# ProProject_ad9959__2024-07-03.net
KiCad netlist of a schematic drawn in EasyEDA Pro
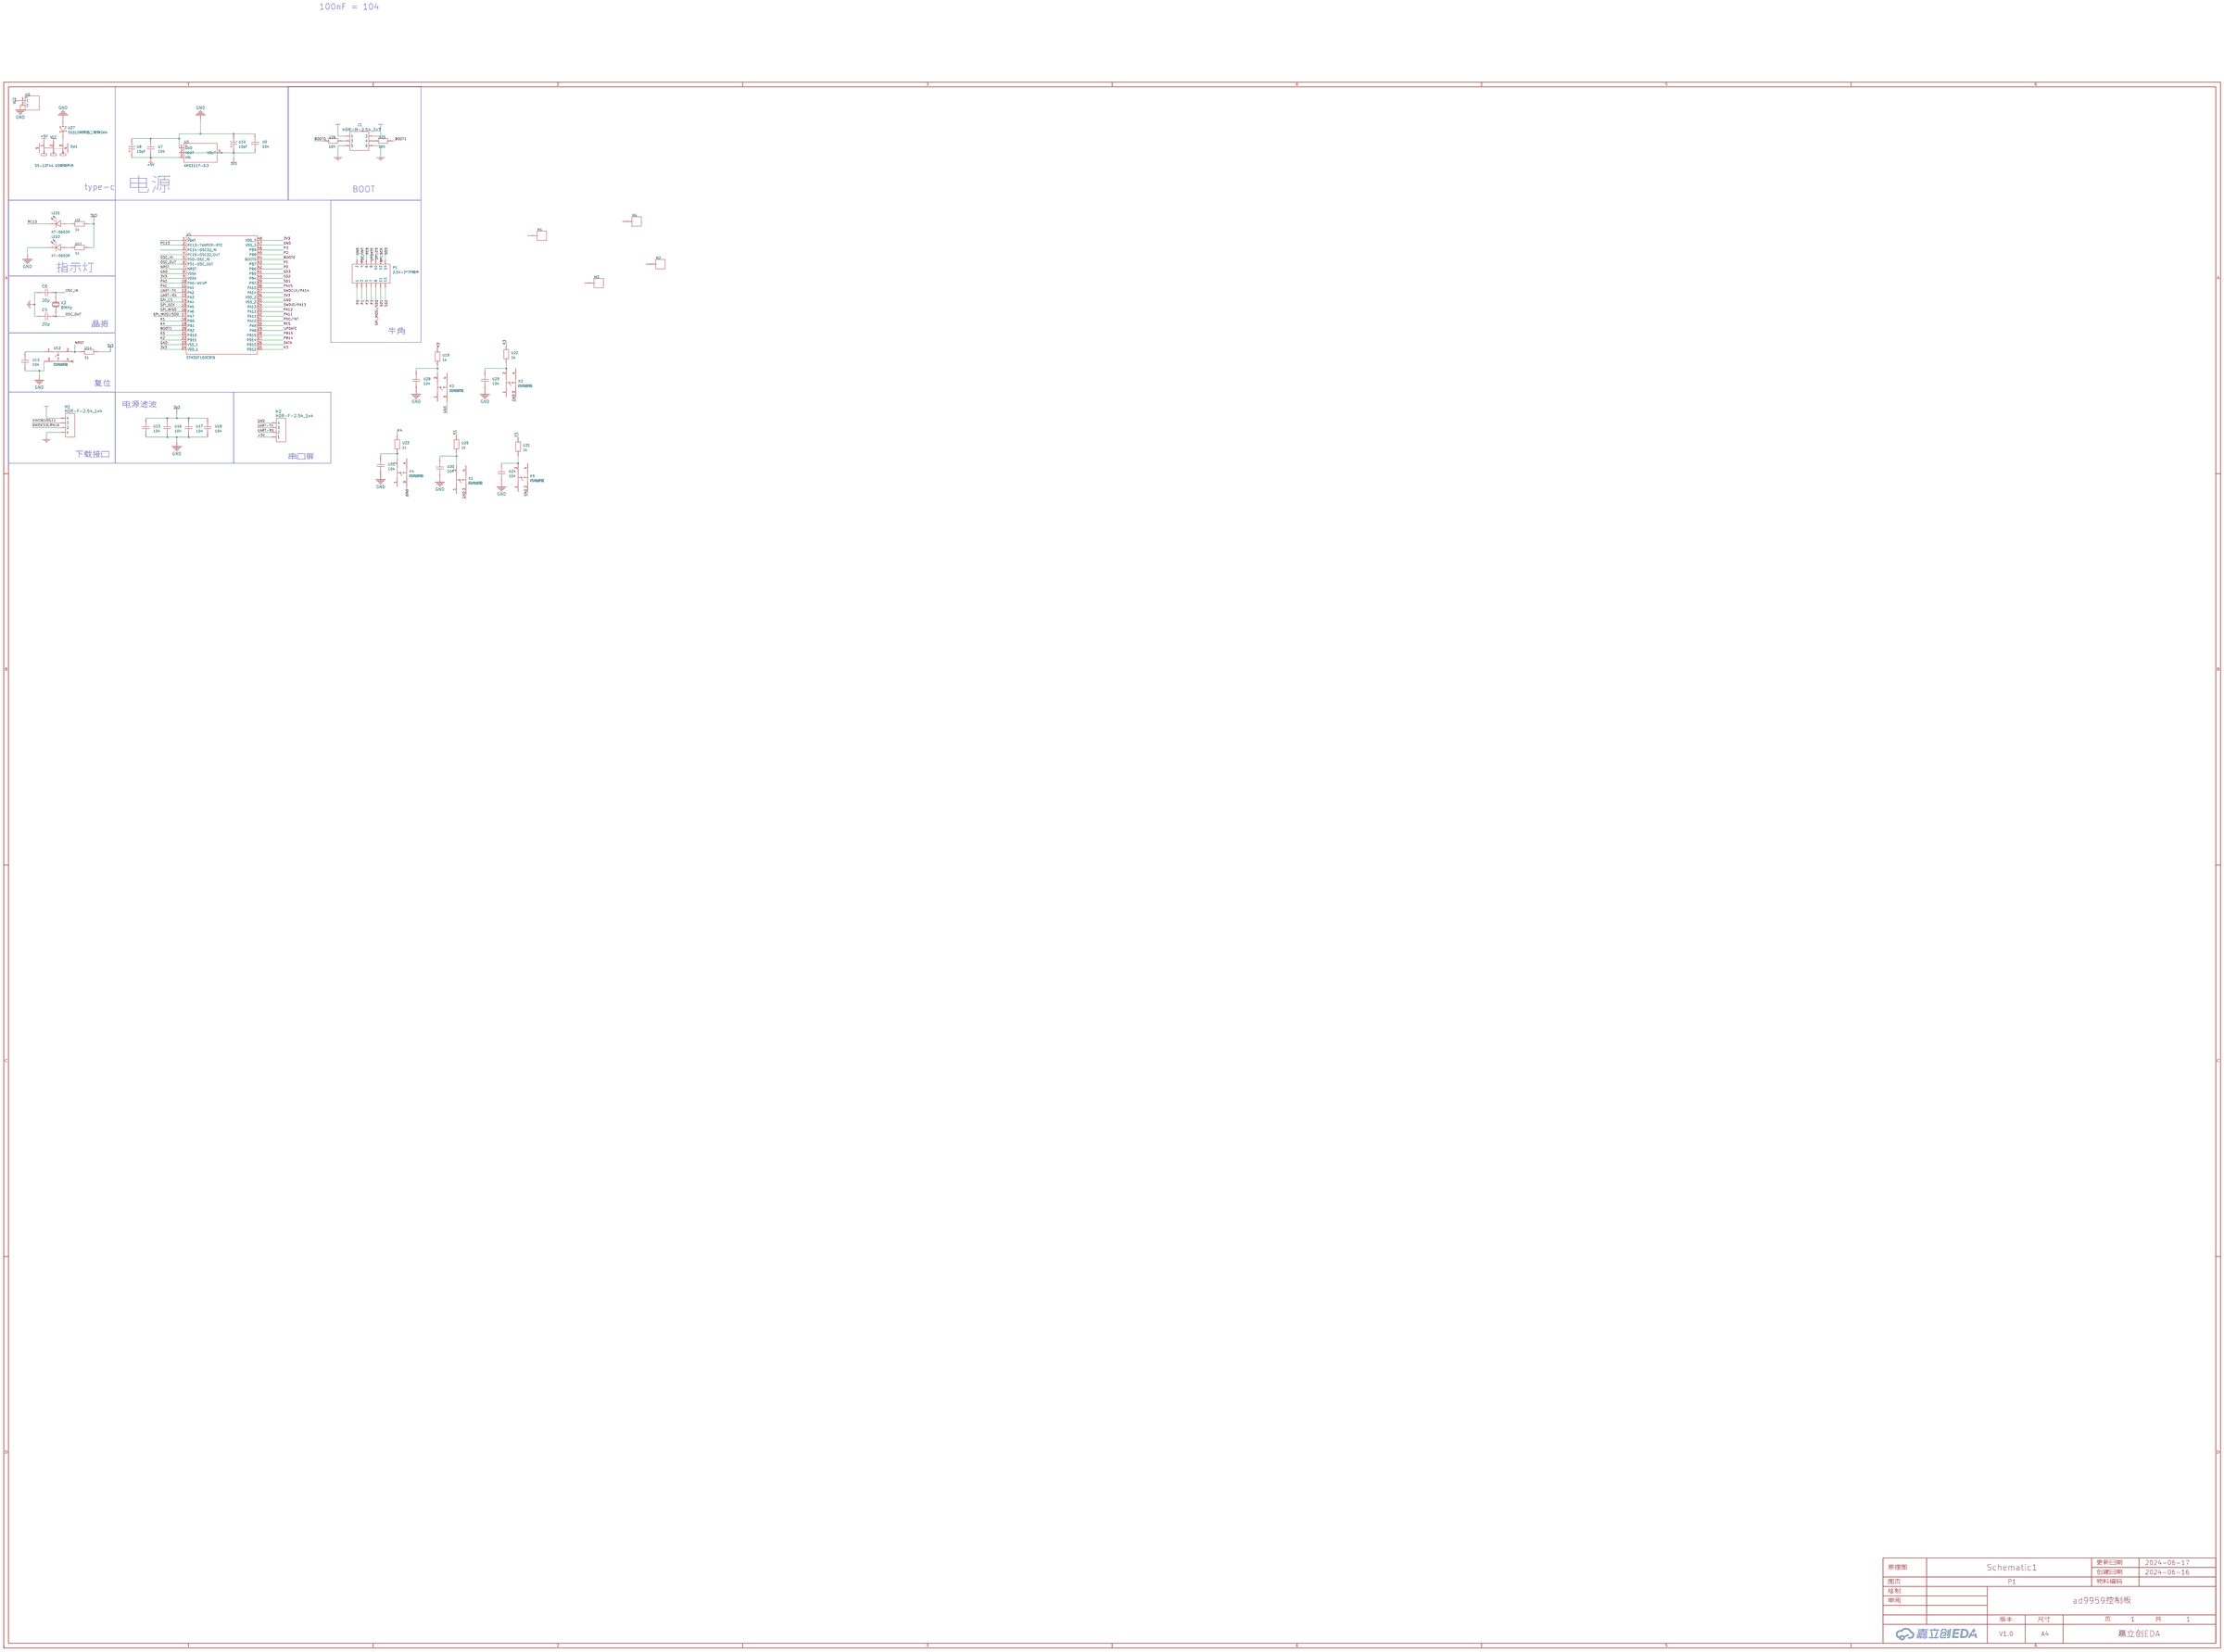
[diagram p0: schematic sheet]

(export (version "E")
  (design (tool "Eeschema 10.0.6"))
  (components
    (comp (ref "C5") (value "20p") (footprint "easyedapro:R0603") (libsource (lib "easyedapro") (part "20p")))
    (comp (ref "C6") (value "20p") (footprint "easyedapro:R0603") (libsource (lib "easyedapro") (part "20p")))
    (comp (ref "H1")
      (value "HDR-F-2.54_1x4")
      (footprint "easyedapro:HDR-F-2.54_1X4")
      (libsource (lib "easyedapro") (part "HDR-F-2.54_1x4"))
    )
    (comp (ref "H2")
      (value "HDR-F-2.54_1x4")
      (footprint "easyedapro:HDR-F-2.54_1X4")
      (libsource (lib "easyedapro") (part "HDR-F-2.54_1x4"))
    )
    (comp (ref "H3")
      (value "~")
      (footprint "easyedapro:HDR-TH_2P-P2.54-V-M-1")
      (libsource (lib "easyedapro") (part "210S-1*2P L=11.6MMGold-plated black"))
    )
    (comp (ref "J1")
      (value "HDR-M-2.54_2x3")
      (footprint "easyedapro:HDR-M-2.54_2X3")
      (libsource (lib "easyedapro") (part "HDR-M-2.54_2x3"))
    )
    (comp (ref "K1")
      (value "四角按键")
      (footprint "easyedapro:SW-SMD_4P-L6.0-W6.0-P4.50-LS9.2")
      (libsource (lib "easyedapro") (part "四角按键"))
    )
    (comp (ref "K2")
      (value "四角按键")
      (footprint "easyedapro:SW-SMD_4P-L6.0-W6.0-P4.50-LS9.2")
      (libsource (lib "easyedapro") (part "四角按键"))
    )
    (comp (ref "K3")
      (value "四角按键")
      (footprint "easyedapro:SW-SMD_4P-L6.0-W6.0-P4.50-LS9.2")
      (libsource (lib "easyedapro") (part "四角按键"))
    )
    (comp (ref "K4")
      (value "四角按键")
      (footprint "easyedapro:SW-SMD_4P-L6.0-W6.0-P4.50-LS9.2")
      (libsource (lib "easyedapro") (part "四角按键"))
    )
    (comp (ref "K5")
      (value "四角按键")
      (footprint "easyedapro:SW-SMD_4P-L6.0-W6.0-P4.50-LS9.2")
      (libsource (lib "easyedapro") (part "四角按键"))
    )
    (comp (ref "LED1")
      (value "KT-0603R")
      (footprint "easyedapro:LED0603-RD")
      (description "发光颜色:红色;功率:-;正向电流:-;主波长:-;二极管配置:-;透镜颜色:-;色温:-;发光角度:-;载带方式:-;工作温度:-40°C~+85°C;")
      (fields (field (name "Manufacturer") "KENTO"))
      (libsource (lib "easyedapro") (part "KT-0603R"))
    )
    (comp (ref "LED2")
      (value "KT-0603R")
      (footprint "easyedapro:LED0603-RD")
      (description "发光颜色:红色;功率:-;正向电流:-;主波长:-;二极管配置:-;透镜颜色:-;色温:-;发光角度:-;载带方式:-;工作温度:-40°C~+85°C;")
      (fields (field (name "Manufacturer") "KENTO"))
      (libsource (lib "easyedapro") (part "KT-0603R"))
    )
    (comp (ref "M1") (value "~") (footprint "easyedapro:M3定位孔") (libsource (lib "easyedapro") (part "定位孔")))
    (comp (ref "M2") (value "~") (footprint "easyedapro:M3定位孔") (libsource (lib "easyedapro") (part "定位孔")))
    (comp (ref "M3") (value "~") (footprint "easyedapro:M3定位孔") (libsource (lib "easyedapro") (part "定位孔")))
    (comp (ref "M4") (value "~") (footprint "easyedapro:M3定位孔") (libsource (lib "easyedapro") (part "定位孔")))
    (comp (ref "P1")
      (value "2.54-2*7P简牛")
      (footprint "easyedapro:IDC-TH_14P-P2.54-V-R2-C7-S2.54")
      (description "连接器类型:简牛座;间距:2.54mm;结构:2x7P;封装形式:直插;行距:2.54mm;排数:2;每排PIN数:7;触头材质:黄铜;触头镀层:金;")
      (fields (field (name "Manufacturer") "BOOMELE(博穆精密)"))
      (libsource (lib "easyedapro") (part "2.54-2*7P简牛"))
    )
    (comp (ref "SW1")
      (value "SS-12F44 G5拨动开关")
      (footprint "easyedapro:SW-TH_SS-12F44-G5")
      (description "拨动开关，柄高5mm")
      (libsource (lib "easyedapro") (part "SS-12F44-G5_C22465"))
    )
    (comp (ref "U1")
      (value "STM32F103C8T6")
      (footprint "easyedapro:LQFP-48_L7.0-W7.0-P0.50-LS9.0-BL")
      (description "CPU内核:ARM-M3;程序存储容量:64KB;RAM总容量:20KB;GPIO端口数量:37;工作电压范围:2V~3.6V;CPU最大主频:72MHz;程序存储器类型:FLASH;")
      (fields (field (name "Manufacturer") "ST(意法半导体)"))
      (libsource (lib "easyedapro") (part "STM32F103C8T6"))
    )
    (comp (ref "U3")
      (value "1k")
      (footprint "easyedapro:R0603")
      (description "电阻类型:薄膜电阻;阻值:7.41kΩ;精度:±0.5%;功率:100mW;温度系数:±50ppm/°C;")
      (fields (field (name "Manufacturer Part") "RT0603DRE077K41L") (field (name "Manufacturer") "YAGEO(国巨)"))
      (libsource (lib "easyedapro") (part "RT0603DRE077K41L"))
    )
    (comp (ref "U5")
      (value "AMS1117-3.3")
      (footprint "easyedapro:SOT-223-3_L6.5-W3.4-P2.30-LS7.0-BR")
      (description "输出类型:固定;最大输入电压:-;输出电压:3.3V;最大输出电流:1A;电源纹波抑制比(PSRR):72dB@(120Hz);输出极性:正极;")
      (fields (field (name "Manufacturer") "AMS"))
      (libsource (lib "easyedapro") (part "AMS1117-3.3"))
    )
    (comp (ref "U7")
      (value "104")
      (footprint "easyedapro:C0603")
      (description "容值:100nF;精度:±5%;额定电压:16V;材质(温度系数):X7R;")
      (fields (field (name "Manufacturer Part") "0603YC104JAT4A") (field (name "Manufacturer") "Kyocera AVX"))
      (libsource (lib "easyedapro") (part "0603YC104JAT4A_C2169226"))
    )
    (comp (ref "U8")
      (value "10pF")
      (footprint "easyedapro:CAP-SMD_L3.6-W1.8-FD")
      (description "容值:2.2uF;精度:±10%;额定电压:20V;等效串联电阻:-;")
      (fields (field (name "Manufacturer Part") "195D225X9020S2T") (field (name "Manufacturer") "VISHAY(威世)"))
      (libsource (lib "easyedapro") (part "195D225X9020S2T"))
    )
    (comp (ref "U9")
      (value "104")
      (footprint "easyedapro:C0603")
      (description "容值:100nF;精度:±5%;额定电压:16V;材质(温度系数):X7R;")
      (fields (field (name "Manufacturer Part") "0603YC104JAT4A") (field (name "Manufacturer") "Kyocera AVX"))
      (libsource (lib "easyedapro") (part "0603YC104JAT4A_C2169226"))
    )
    (comp (ref "U10")
      (value "10pF")
      (footprint "easyedapro:CAP-SMD_L3.6-W1.8-FD")
      (description "容值:2.2uF;精度:±10%;额定电压:20V;等效串联电阻:-;")
      (fields (field (name "Manufacturer Part") "195D225X9020S2T") (field (name "Manufacturer") "VISHAY(威世)"))
      (libsource (lib "easyedapro") (part "195D225X9020S2T"))
    )
    (comp (ref "U11")
      (value "1k")
      (footprint "easyedapro:R0603")
      (description "电阻类型:薄膜电阻;阻值:7.41kΩ;精度:±0.5%;功率:100mW;温度系数:±50ppm/°C;")
      (fields (field (name "Manufacturer Part") "RT0603DRE077K41L") (field (name "Manufacturer") "YAGEO(国巨)"))
      (libsource (lib "easyedapro") (part "RT0603DRE077K41L"))
    )
    (comp (ref "U12")
      (value "四角按键")
      (footprint "easyedapro:SW-SMD_4P-L6.0-W6.0-P4.50-LS9.2")
      (libsource (lib "easyedapro") (part "四角按键"))
    )
    (comp (ref "U13")
      (value "104")
      (footprint "easyedapro:C0603")
      (description "容值:100nF;精度:±5%;额定电压:16V;材质(温度系数):X7R;")
      (fields (field (name "Manufacturer Part") "0603YC104JAT4A") (field (name "Manufacturer") "Kyocera AVX"))
      (libsource (lib "easyedapro") (part "0603YC104JAT4A_C2169226"))
    )
    (comp (ref "U14")
      (value "1k")
      (footprint "easyedapro:R0603")
      (description "电阻类型:薄膜电阻;阻值:7.41kΩ;精度:±0.5%;功率:100mW;温度系数:±50ppm/°C;")
      (fields (field (name "Manufacturer Part") "RT0603DRE077K41L") (field (name "Manufacturer") "YAGEO(国巨)"))
      (libsource (lib "easyedapro") (part "RT0603DRE077K41L"))
    )
    (comp (ref "U15")
      (value "104")
      (footprint "easyedapro:C0603")
      (description "容值:100nF;精度:±5%;额定电压:16V;材质(温度系数):X7R;")
      (fields (field (name "Manufacturer Part") "0603YC104JAT4A") (field (name "Manufacturer") "Kyocera AVX"))
      (libsource (lib "easyedapro") (part "0603YC104JAT4A_C2169226"))
    )
    (comp (ref "U16")
      (value "104")
      (footprint "easyedapro:C0603")
      (description "容值:100nF;精度:±5%;额定电压:16V;材质(温度系数):X7R;")
      (fields (field (name "Manufacturer Part") "0603YC104JAT4A") (field (name "Manufacturer") "Kyocera AVX"))
      (libsource (lib "easyedapro") (part "0603YC104JAT4A_C2169226"))
    )
    (comp (ref "U17")
      (value "104")
      (footprint "easyedapro:C0603")
      (description "容值:100nF;精度:±5%;额定电压:16V;材质(温度系数):X7R;")
      (fields (field (name "Manufacturer Part") "0603YC104JAT4A") (field (name "Manufacturer") "Kyocera AVX"))
      (libsource (lib "easyedapro") (part "0603YC104JAT4A_C2169226"))
    )
    (comp (ref "U18")
      (value "104")
      (footprint "easyedapro:C0603")
      (description "容值:100nF;精度:±5%;额定电压:16V;材质(温度系数):X7R;")
      (fields (field (name "Manufacturer Part") "0603YC104JAT4A") (field (name "Manufacturer") "Kyocera AVX"))
      (libsource (lib "easyedapro") (part "0603YC104JAT4A_C2169226"))
    )
    (comp (ref "U19")
      (value "1k")
      (footprint "easyedapro:R0603")
      (description "电阻类型:薄膜电阻;阻值:7.41kΩ;精度:±0.5%;功率:100mW;温度系数:±50ppm/°C;")
      (fields (field (name "Manufacturer Part") "RT0603DRE077K41L") (field (name "Manufacturer") "YAGEO(国巨)"))
      (libsource (lib "easyedapro") (part "RT0603DRE077K41L"))
    )
    (comp (ref "U20")
      (value "1k")
      (footprint "easyedapro:R0603")
      (description "电阻类型:薄膜电阻;阻值:7.41kΩ;精度:±0.5%;功率:100mW;温度系数:±50ppm/°C;")
      (fields (field (name "Manufacturer Part") "RT0603DRE077K41L") (field (name "Manufacturer") "YAGEO(国巨)"))
      (libsource (lib "easyedapro") (part "RT0603DRE077K41L"))
    )
    (comp (ref "U21")
      (value "1k")
      (footprint "easyedapro:R0603")
      (description "电阻类型:薄膜电阻;阻值:7.41kΩ;精度:±0.5%;功率:100mW;温度系数:±50ppm/°C;")
      (fields (field (name "Manufacturer Part") "RT0603DRE077K41L") (field (name "Manufacturer") "YAGEO(国巨)"))
      (libsource (lib "easyedapro") (part "RT0603DRE077K41L"))
    )
    (comp (ref "U22")
      (value "1k")
      (footprint "easyedapro:R0603")
      (description "电阻类型:薄膜电阻;阻值:7.41kΩ;精度:±0.5%;功率:100mW;温度系数:±50ppm/°C;")
      (fields (field (name "Manufacturer Part") "RT0603DRE077K41L") (field (name "Manufacturer") "YAGEO(国巨)"))
      (libsource (lib "easyedapro") (part "RT0603DRE077K41L"))
    )
    (comp (ref "U23")
      (value "1k")
      (footprint "easyedapro:R0603")
      (description "电阻类型:薄膜电阻;阻值:7.41kΩ;精度:±0.5%;功率:100mW;温度系数:±50ppm/°C;")
      (fields (field (name "Manufacturer Part") "RT0603DRE077K41L") (field (name "Manufacturer") "YAGEO(国巨)"))
      (libsource (lib "easyedapro") (part "RT0603DRE077K41L"))
    )
    (comp (ref "U24")
      (value "104")
      (footprint "easyedapro:C0603")
      (description "容值:100nF;精度:±5%;额定电压:16V;材质(温度系数):X7R;")
      (fields (field (name "Manufacturer Part") "0603YC104JAT4A") (field (name "Manufacturer") "Kyocera AVX"))
      (libsource (lib "easyedapro") (part "0603YC104JAT4A_C2169226"))
    )
    (comp (ref "U25")
      (value "10K")
      (footprint "easyedapro:R0603")
      (description "电阻类型:薄膜电阻;阻值:7.41kΩ;精度:±0.5%;功率:100mW;温度系数:±50ppm/°C;")
      (fields (field (name "Manufacturer Part") "RT0603DRE077K41L") (field (name "Manufacturer") "YAGEO(国巨)"))
      (libsource (lib "easyedapro") (part "RT0603DRE077K41L"))
    )
    (comp (ref "U26")
      (value "10K")
      (footprint "easyedapro:R0603")
      (description "电阻类型:薄膜电阻;阻值:7.41kΩ;精度:±0.5%;功率:100mW;温度系数:±50ppm/°C;")
      (fields (field (name "Manufacturer Part") "RT0603DRE077K41L") (field (name "Manufacturer") "YAGEO(国巨)"))
      (libsource (lib "easyedapro") (part "RT0603DRE077K41L"))
    )
    (comp (ref "U27")
      (value "SS310肖特基二极管SMA")
      (footprint "easyedapro:SMA_L4.3-W2.6-LS5.1-R-RD")
      (libsource (lib "easyedapro") (part "SS310肖特基二极管SMA"))
    )
    (comp (ref "U28")
      (value "104")
      (footprint "easyedapro:C0603")
      (description "容值:100nF;精度:±5%;额定电压:16V;材质(温度系数):X7R;")
      (fields (field (name "Manufacturer Part") "0603YC104JAT4A") (field (name "Manufacturer") "Kyocera AVX"))
      (libsource (lib "easyedapro") (part "0603YC104JAT4A_C2169226"))
    )
    (comp (ref "U29")
      (value "104")
      (footprint "easyedapro:C0603")
      (description "容值:100nF;精度:±5%;额定电压:16V;材质(温度系数):X7R;")
      (fields (field (name "Manufacturer Part") "0603YC104JAT4A") (field (name "Manufacturer") "Kyocera AVX"))
      (libsource (lib "easyedapro") (part "0603YC104JAT4A_C2169226"))
    )
    (comp (ref "U30")
      (value "104")
      (footprint "easyedapro:C0603")
      (description "容值:100nF;精度:±5%;额定电压:16V;材质(温度系数):X7R;")
      (fields (field (name "Manufacturer Part") "0603YC104JAT4A") (field (name "Manufacturer") "Kyocera AVX"))
      (libsource (lib "easyedapro") (part "0603YC104JAT4A_C2169226"))
    )
    (comp (ref "U31")
      (value "104")
      (footprint "easyedapro:C0603")
      (description "容值:100nF;精度:±5%;额定电压:16V;材质(温度系数):X7R;")
      (fields (field (name "Manufacturer Part") "0603YC104JAT4A") (field (name "Manufacturer") "Kyocera AVX"))
      (libsource (lib "easyedapro") (part "0603YC104JAT4A_C2169226"))
    )
    (comp (ref "X2")
      (value "8MHz")
      (footprint "easyedapro:HC-49US_L11.5-W4.5-P4.88")
      (fields
        (field (name "Manufacturer Part") "B08000J067")
        (field (name "Manufacturer") "ZheJiang East Crystal Elec")
      )
      (libsource (lib "easyedapro") (part "8MHz"))
    )
  )
  (nets
    (net (code "1") (name "+5V") (class "Default")
      (node (ref "H2") (pin "4") (pinfunction "1_4") (pintype "input"))
      (node (ref "SW1") (pin "1") (pinfunction "1_1") (pintype "unspecified"))
      (node (ref "U5") (pin "3") (pinfunction "VIN_3") (pintype "unspecified"))
      (node (ref "U7") (pin "1") (pinfunction "1_1") (pintype "unspecified"))
      (node (ref "U8") (pin "1") (pinfunction "1_1") (pintype "input"))
    )
    (net (code "2") (name "/BOOT0") (class "Default")
      (node (ref "U1") (pin "44") (pinfunction "BOOT0_44") (pintype "unspecified"))
      (node (ref "U26") (pin "1") (pinfunction "1_1") (pintype "unspecified"))
    )
    (net (code "3") (name "/BOOT1") (class "Default")
      (node (ref "U1") (pin "20") (pinfunction "PB2_20") (pintype "unspecified"))
      (node (ref "U25") (pin "2") (pinfunction "2_2") (pintype "unspecified"))
    )
    (net (code "4") (name "/DATA") (class "Default")
      (node (ref "U1") (pin "26") (pinfunction "PB13_26") (pintype "unspecified"))
    )
    (net (code "5") (name "/K1") (class "Default")
      (node (ref "U1") (pin "18") (pinfunction "PB0_18") (pintype "unspecified"))
      (node (ref "U20") (pin "2") (pinfunction "2_2") (pintype "unspecified"))
    )
    (net (code "6") (name "/K2") (class "Default")
      (node (ref "U1") (pin "22") (pinfunction "PB11_22") (pintype "unspecified"))
      (node (ref "U19") (pin "1") (pinfunction "1_1") (pintype "unspecified"))
    )
    (net (code "7") (name "/K3") (class "Default")
      (node (ref "U1") (pin "25") (pinfunction "PB12_25") (pintype "unspecified"))
      (node (ref "U22") (pin "2") (pinfunction "2_2") (pintype "unspecified"))
    )
    (net (code "8") (name "/K4") (class "Default")
      (node (ref "U1") (pin "19") (pinfunction "PB1_19") (pintype "unspecified"))
      (node (ref "U23") (pin "2") (pinfunction "2_2") (pintype "unspecified"))
    )
    (net (code "9") (name "/K5") (class "Default")
      (node (ref "U1") (pin "21") (pinfunction "PB10_21") (pintype "unspecified"))
      (node (ref "U21") (pin "2") (pinfunction "2_2") (pintype "unspecified"))
    )
    (net (code "10") (name "/NRST") (class "Default")
      (node (ref "U1") (pin "7") (pinfunction "NRST_7") (pintype "unspecified"))
      (node (ref "U12") (pin "2") (pinfunction "2_2") (pintype "unspecified"))
      (node (ref "U14") (pin "1") (pinfunction "1_1") (pintype "unspecified"))
    )
    (net (code "11") (name "/OSC_IN") (class "Default")
      (node (ref "C6") (pin "2") (pinfunction "2_2") (pintype "input"))
      (node (ref "U1") (pin "5") (pinfunction "PD0-OSC_IN_5") (pintype "unspecified"))
      (node (ref "X2") (pin "1") (pinfunction "OSC1_1") (pintype "input"))
    )
    (net (code "12") (name "/OSC_OUT") (class "Default")
      (node (ref "C5") (pin "2") (pinfunction "2_2") (pintype "input"))
      (node (ref "U1") (pin "6") (pinfunction "PD1-OSC_OUT_6") (pintype "unspecified"))
      (node (ref "X2") (pin "2") (pinfunction "OSC2_2") (pintype "input"))
    )
    (net (code "13") (name "/P0") (class "Default")
      (node (ref "P1") (pin "1") (pinfunction "1_1") (pintype "input"))
      (node (ref "U1") (pin "42") (pinfunction "PB6_42") (pintype "unspecified"))
    )
    (net (code "14") (name "/P1") (class "Default")
      (node (ref "P1") (pin "3") (pinfunction "3_3") (pintype "input"))
      (node (ref "U1") (pin "43") (pinfunction "PB7_43") (pintype "unspecified"))
    )
    (net (code "15") (name "/P2") (class "Default")
      (node (ref "P1") (pin "5") (pinfunction "5_5") (pintype "input"))
      (node (ref "U1") (pin "45") (pinfunction "PB8_45") (pintype "unspecified"))
    )
    (net (code "16") (name "/P3") (class "Default")
      (node (ref "P1") (pin "7") (pinfunction "7_7") (pintype "input"))
      (node (ref "U1") (pin "46") (pinfunction "PB9_46") (pintype "unspecified"))
    )
    (net (code "17") (name "/PA0") (class "Default")
      (node (ref "U1") (pin "10") (pinfunction "PA0-WKUP_10") (pintype "unspecified"))
    )
    (net (code "18") (name "/PA1") (class "Default")
      (node (ref "U1") (pin "11") (pinfunction "PA1_11") (pintype "unspecified"))
    )
    (net (code "19") (name "/PA11") (class "Default")
      (node (ref "U1") (pin "32") (pinfunction "PA11_32") (pintype "unspecified"))
    )
    (net (code "20") (name "/PA12") (class "Default")
      (node (ref "U1") (pin "33") (pinfunction "PA12_33") (pintype "unspecified"))
    )
    (net (code "21") (name "/PA15") (class "Default")
      (node (ref "U1") (pin "38") (pinfunction "PA15_38") (pintype "unspecified"))
    )
    (net (code "22") (name "/PB14") (class "Default")
      (node (ref "U1") (pin "27") (pinfunction "PB14_27") (pintype "unspecified"))
    )
    (net (code "23") (name "/PB15") (class "Default")
      (node (ref "U1") (pin "28") (pinfunction "PB15_28") (pintype "unspecified"))
    )
    (net (code "24") (name "/PC13") (class "Default")
      (node (ref "LED1") (pin "1") (pinfunction "K_1") (pintype "input"))
      (node (ref "U1") (pin "2") (pinfunction "PC13-TAMPER-RTC_2") (pintype "unspecified"))
    )
    (net (code "25") (name "/PDC{slash}INT") (class "Default")
      (node (ref "P1") (pin "4") (pinfunction "4_4") (pintype "input"))
      (node (ref "U1") (pin "31") (pinfunction "PA10_31") (pintype "unspecified"))
    )
    (net (code "26") (name "/RES") (class "Default")
      (node (ref "P1") (pin "6") (pinfunction "6_6") (pintype "input"))
      (node (ref "U1") (pin "30") (pinfunction "PA9_30") (pintype "unspecified"))
    )
    (net (code "27") (name "/SD1") (class "Default")
      (node (ref "P1") (pin "11") (pinfunction "11_11") (pintype "input"))
      (node (ref "U1") (pin "39") (pinfunction "PB3_39") (pintype "unspecified"))
    )
    (net (code "28") (name "/SD2") (class "Default")
      (node (ref "P1") (pin "13") (pinfunction "13_13") (pintype "input"))
      (node (ref "U1") (pin "40") (pinfunction "PB4_40") (pintype "unspecified"))
    )
    (net (code "29") (name "/SD3") (class "Default")
      (node (ref "P1") (pin "14") (pinfunction "14_14") (pintype "input"))
      (node (ref "U1") (pin "41") (pinfunction "PB5_41") (pintype "unspecified"))
    )
    (net (code "30") (name "/SPI_CS") (class "Default")
      (node (ref "P1") (pin "10") (pinfunction "10_10") (pintype "input"))
      (node (ref "U1") (pin "14") (pinfunction "PA4_14") (pintype "unspecified"))
    )
    (net (code "31") (name "/SPI_MISO") (class "Default")
      (node (ref "U1") (pin "16") (pinfunction "PA6_16") (pintype "unspecified"))
    )
    (net (code "32") (name "/SPI_MOSI{slash}SD0") (class "Default")
      (node (ref "P1") (pin "9") (pinfunction "9_9") (pintype "input"))
      (node (ref "U1") (pin "17") (pinfunction "PA7_17") (pintype "unspecified"))
    )
    (net (code "33") (name "/SPI_SCK") (class "Default")
      (node (ref "P1") (pin "12") (pinfunction "12_12") (pintype "input"))
      (node (ref "U1") (pin "15") (pinfunction "PA5_15") (pintype "unspecified"))
    )
    (net (code "34") (name "/SWDCLK{slash}PA14") (class "Default")
      (node (ref "H1") (pin "3") (pinfunction "2_3") (pintype "input"))
      (node (ref "U1") (pin "37") (pinfunction "PA14_37") (pintype "unspecified"))
    )
    (net (code "35") (name "/SWDIO{slash}PA13") (class "Default")
      (node (ref "H1") (pin "2") (pinfunction "3_2") (pintype "input"))
      (node (ref "U1") (pin "34") (pinfunction "PA13_34") (pintype "unspecified"))
    )
    (net (code "36") (name "/UART-RX") (class "Default")
      (node (ref "H2") (pin "3") (pinfunction "2_3") (pintype "input"))
      (node (ref "U1") (pin "13") (pinfunction "PA3_13") (pintype "unspecified"))
    )
    (net (code "37") (name "/UART-TX") (class "Default")
      (node (ref "H2") (pin "2") (pinfunction "3_2") (pintype "input"))
      (node (ref "U1") (pin "12") (pinfunction "PA2_12") (pintype "unspecified"))
    )
    (net (code "38") (name "/UPDATE") (class "Default")
      (node (ref "P1") (pin "8") (pinfunction "8_8") (pintype "input"))
      (node (ref "U1") (pin "29") (pinfunction "PA8_29") (pintype "unspecified"))
    )
    (net (code "39") (name "3V3") (class "Default")
      (node (ref "H1") (pin "1") (pinfunction "4_1") (pintype "input"))
      (node (ref "J1") (pin "1") (pinfunction "1_1") (pintype "input"))
      (node (ref "J1") (pin "2") (pinfunction "2_2") (pintype "input"))
      (node (ref "U1") (pin "24") (pinfunction "VDD_1_24") (pintype "unspecified"))
      (node (ref "U1") (pin "36") (pinfunction "VDD_2_36") (pintype "unspecified"))
      (node (ref "U1") (pin "48") (pinfunction "VDD_3_48") (pintype "unspecified"))
      (node (ref "U1") (pin "9") (pinfunction "VDDA_9") (pintype "unspecified"))
      (node (ref "U10") (pin "1") (pinfunction "1_1") (pintype "input"))
      (node (ref "U11") (pin "2") (pinfunction "2_2") (pintype "unspecified"))
      (node (ref "U14") (pin "2") (pinfunction "2_2") (pintype "unspecified"))
      (node (ref "U15") (pin "1") (pinfunction "1_1") (pintype "unspecified"))
      (node (ref "U16") (pin "1") (pinfunction "1_1") (pintype "unspecified"))
      (node (ref "U17") (pin "1") (pinfunction "1_1") (pintype "unspecified"))
      (node (ref "U18") (pin "1") (pinfunction "1_1") (pintype "unspecified"))
      (node (ref "U3") (pin "2") (pinfunction "2_2") (pintype "unspecified"))
      (node (ref "U5") (pin "2") (pinfunction "VOUT_2") (pintype "unspecified"))
      (node (ref "U5") (pin "4") (pinfunction "VOUT_4") (pintype "unspecified"))
      (node (ref "U9") (pin "1") (pinfunction "1_1") (pintype "unspecified"))
    )
    (net (code "40") (name "GND") (class "Default")
      (node (ref "C5") (pin "1") (pinfunction "1_1") (pintype "input"))
      (node (ref "C6") (pin "1") (pinfunction "1_1") (pintype "input"))
      (node (ref "H1") (pin "4") (pinfunction "1_4") (pintype "input"))
      (node (ref "H2") (pin "1") (pinfunction "4_1") (pintype "input"))
      (node (ref "H3") (pin "2") (pinfunction "2_2") (pintype "unspecified"))
      (node (ref "J1") (pin "5") (pinfunction "5_5") (pintype "input"))
      (node (ref "J1") (pin "6") (pinfunction "6_6") (pintype "input"))
      (node (ref "K1") (pin "3") (pinfunction "3_3") (pintype "unspecified"))
      (node (ref "K2") (pin "3") (pinfunction "3_3") (pintype "unspecified"))
      (node (ref "K3") (pin "3") (pinfunction "3_3") (pintype "unspecified"))
      (node (ref "K4") (pin "3") (pinfunction "3_3") (pintype "unspecified"))
      (node (ref "K5") (pin "3") (pinfunction "3_3") (pintype "unspecified"))
      (node (ref "LED2") (pin "1") (pinfunction "K_1") (pintype "input"))
      (node (ref "P1") (pin "2") (pinfunction "2_2") (pintype "input"))
      (node (ref "U1") (pin "23") (pinfunction "VSS_1_23") (pintype "unspecified"))
      (node (ref "U1") (pin "35") (pinfunction "VSS_2_35") (pintype "unspecified"))
      (node (ref "U1") (pin "47") (pinfunction "VSS_3_47") (pintype "unspecified"))
      (node (ref "U1") (pin "8") (pinfunction "VSSA_8") (pintype "unspecified"))
      (node (ref "U10") (pin "2") (pinfunction "2_2") (pintype "input"))
      (node (ref "U12") (pin "3") (pinfunction "3_3") (pintype "unspecified"))
      (node (ref "U13") (pin "2") (pinfunction "2_2") (pintype "unspecified"))
      (node (ref "U15") (pin "2") (pinfunction "2_2") (pintype "unspecified"))
      (node (ref "U16") (pin "2") (pinfunction "2_2") (pintype "unspecified"))
      (node (ref "U17") (pin "2") (pinfunction "2_2") (pintype "unspecified"))
      (node (ref "U18") (pin "2") (pinfunction "2_2") (pintype "unspecified"))
      (node (ref "U24") (pin "2") (pinfunction "2_2") (pintype "unspecified"))
      (node (ref "U27") (pin "1") (pinfunction "A_1") (pintype "unspecified"))
      (node (ref "U28") (pin "2") (pinfunction "2_2") (pintype "unspecified"))
      (node (ref "U29") (pin "2") (pinfunction "2_2") (pintype "unspecified"))
      (node (ref "U30") (pin "2") (pinfunction "2_2") (pintype "unspecified"))
      (node (ref "U31") (pin "2") (pinfunction "2_2") (pintype "unspecified"))
      (node (ref "U5") (pin "1") (pinfunction "GND_1") (pintype "unspecified"))
      (node (ref "U7") (pin "2") (pinfunction "2_2") (pintype "unspecified"))
      (node (ref "U8") (pin "2") (pinfunction "2_2") (pintype "input"))
      (node (ref "U9") (pin "2") (pinfunction "2_2") (pintype "unspecified"))
    )
    (net (code "41") (name "Net-(J1-Pad3)") (class "Default")
      (node (ref "J1") (pin "3") (pinfunction "3_3") (pintype "input"))
      (node (ref "U26") (pin "2") (pinfunction "2_2") (pintype "unspecified"))
    )
    (net (code "42") (name "Net-(J1-Pad4)") (class "Default")
      (node (ref "J1") (pin "4") (pinfunction "4_4") (pintype "input"))
      (node (ref "U25") (pin "1") (pinfunction "1_1") (pintype "unspecified"))
    )
    (net (code "43") (name "Net-(K1-Pad2)") (class "Default")
      (node (ref "K1") (pin "2") (pinfunction "2_2") (pintype "unspecified"))
      (node (ref "U20") (pin "1") (pinfunction "1_1") (pintype "unspecified"))
      (node (ref "U30") (pin "1") (pinfunction "1_1") (pintype "unspecified"))
    )
    (net (code "44") (name "Net-(K2-Pad2)") (class "Default")
      (node (ref "K2") (pin "2") (pinfunction "2_2") (pintype "unspecified"))
      (node (ref "U19") (pin "2") (pinfunction "2_2") (pintype "unspecified"))
      (node (ref "U28") (pin "1") (pinfunction "1_1") (pintype "unspecified"))
    )
    (net (code "45") (name "Net-(K3-Pad2)") (class "Default")
      (node (ref "K3") (pin "2") (pinfunction "2_2") (pintype "unspecified"))
      (node (ref "U22") (pin "1") (pinfunction "1_1") (pintype "unspecified"))
      (node (ref "U29") (pin "1") (pinfunction "1_1") (pintype "unspecified"))
    )
    (net (code "46") (name "Net-(K4-Pad2)") (class "Default")
      (node (ref "K4") (pin "2") (pinfunction "2_2") (pintype "unspecified"))
      (node (ref "U23") (pin "1") (pinfunction "1_1") (pintype "unspecified"))
      (node (ref "U31") (pin "1") (pinfunction "1_1") (pintype "unspecified"))
    )
    (net (code "47") (name "Net-(K5-Pad2)") (class "Default")
      (node (ref "K5") (pin "2") (pinfunction "2_2") (pintype "unspecified"))
      (node (ref "U21") (pin "1") (pinfunction "1_1") (pintype "unspecified"))
      (node (ref "U24") (pin "1") (pinfunction "1_1") (pintype "unspecified"))
    )
    (net (code "48") (name "Net-(LED1-A)") (class "Default")
      (node (ref "LED1") (pin "2") (pinfunction "A_2") (pintype "input"))
      (node (ref "U3") (pin "1") (pinfunction "1_1") (pintype "unspecified"))
    )
    (net (code "49") (name "Net-(LED2-A)") (class "Default")
      (node (ref "LED2") (pin "2") (pinfunction "A_2") (pintype "input"))
      (node (ref "U11") (pin "1") (pinfunction "1_1") (pintype "unspecified"))
    )
    (net (code "50") (name "Net-(U12-Pad1)") (class "Default")
      (node (ref "U12") (pin "1") (pinfunction "1_1") (pintype "unspecified"))
      (node (ref "U13") (pin "1") (pinfunction "1_1") (pintype "unspecified"))
    )
    (net (code "51") (name "Net-(U27-K)") (class "Default")
      (node (ref "SW1") (pin "3") (pinfunction "3_3") (pintype "unspecified"))
      (node (ref "U27") (pin "2") (pinfunction "K_2") (pintype "unspecified"))
    )
    (net (code "52") (name "VCC") (class "Default")
      (node (ref "H3") (pin "1") (pinfunction "1_1") (pintype "unspecified"))
      (node (ref "SW1") (pin "2") (pinfunction "2_2") (pintype "unspecified"))
    )
    (net (code "53") (name "unconnected-(K1-Pad1)") (class "Default")
      (node (ref "K1") (pin "1") (pinfunction "1_1") (pintype "unspecified"))
    )
    (net (code "54") (name "unconnected-(K1-Pad4)") (class "Default")
      (node (ref "K1") (pin "4") (pinfunction "4_4") (pintype "unspecified"))
    )
    (net (code "55") (name "unconnected-(K2-Pad1)") (class "Default")
      (node (ref "K2") (pin "1") (pinfunction "1_1") (pintype "unspecified"))
    )
    (net (code "56") (name "unconnected-(K2-Pad4)") (class "Default")
      (node (ref "K2") (pin "4") (pinfunction "4_4") (pintype "unspecified"))
    )
    (net (code "57") (name "unconnected-(K3-Pad1)") (class "Default")
      (node (ref "K3") (pin "1") (pinfunction "1_1") (pintype "unspecified"))
    )
    (net (code "58") (name "unconnected-(K3-Pad4)") (class "Default")
      (node (ref "K3") (pin "4") (pinfunction "4_4") (pintype "unspecified"))
    )
    (net (code "59") (name "unconnected-(K4-Pad1)") (class "Default")
      (node (ref "K4") (pin "1") (pinfunction "1_1") (pintype "unspecified"))
    )
    (net (code "60") (name "unconnected-(K4-Pad4)") (class "Default")
      (node (ref "K4") (pin "4") (pinfunction "4_4") (pintype "unspecified"))
    )
    (net (code "61") (name "unconnected-(K5-Pad1)") (class "Default")
      (node (ref "K5") (pin "1") (pinfunction "1_1") (pintype "unspecified"))
    )
    (net (code "62") (name "unconnected-(K5-Pad4)") (class "Default")
      (node (ref "K5") (pin "4") (pinfunction "4_4") (pintype "unspecified"))
    )
    (net (code "63") (name "unconnected-(M1-Pad1)") (class "Default")
      (node (ref "M1") (pin "1") (pinfunction "1_1") (pintype "input"))
    )
    (net (code "64") (name "unconnected-(M2-Pad1)") (class "Default")
      (node (ref "M2") (pin "1") (pinfunction "1_1") (pintype "input"))
    )
    (net (code "65") (name "unconnected-(M3-Pad1)") (class "Default")
      (node (ref "M3") (pin "1") (pinfunction "1_1") (pintype "input"))
    )
    (net (code "66") (name "unconnected-(M4-Pad1)") (class "Default")
      (node (ref "M4") (pin "1") (pinfunction "1_1") (pintype "input"))
    )
    (net (code "67") (name "unconnected-(SW1-Pad4)") (class "Default")
      (node (ref "SW1") (pin "4") (pinfunction "4_4") (pintype "unspecified"))
    )
    (net (code "68") (name "unconnected-(SW1-Pad5)") (class "Default")
      (node (ref "SW1") (pin "5") (pinfunction "5_5") (pintype "unspecified"))
    )
    (net (code "69") (name "unconnected-(U1-PC14-OSC32_IN-Pad3)") (class "Default")
      (node (ref "U1") (pin "3") (pinfunction "PC14-OSC32_IN_3") (pintype "unspecified"))
    )
    (net (code "70") (name "unconnected-(U1-PC15-OSC32_OUT-Pad4)") (class "Default")
      (node (ref "U1") (pin "4") (pinfunction "PC15-OSC32_OUT_4") (pintype "unspecified"))
    )
    (net (code "71") (name "unconnected-(U1-VBAT-Pad1)") (class "Default")
      (node (ref "U1") (pin "1") (pinfunction "VBAT_1") (pintype "unspecified"))
    )
    (net (code "72") (name "unconnected-(U12-Pad4)") (class "Default")
      (node (ref "U12") (pin "4") (pinfunction "4_4") (pintype "unspecified+no_connect"))
    )
  )
)
